# 05_-_PROFINET.net
KiCad netlist of a schematic drawn in Altium Designer
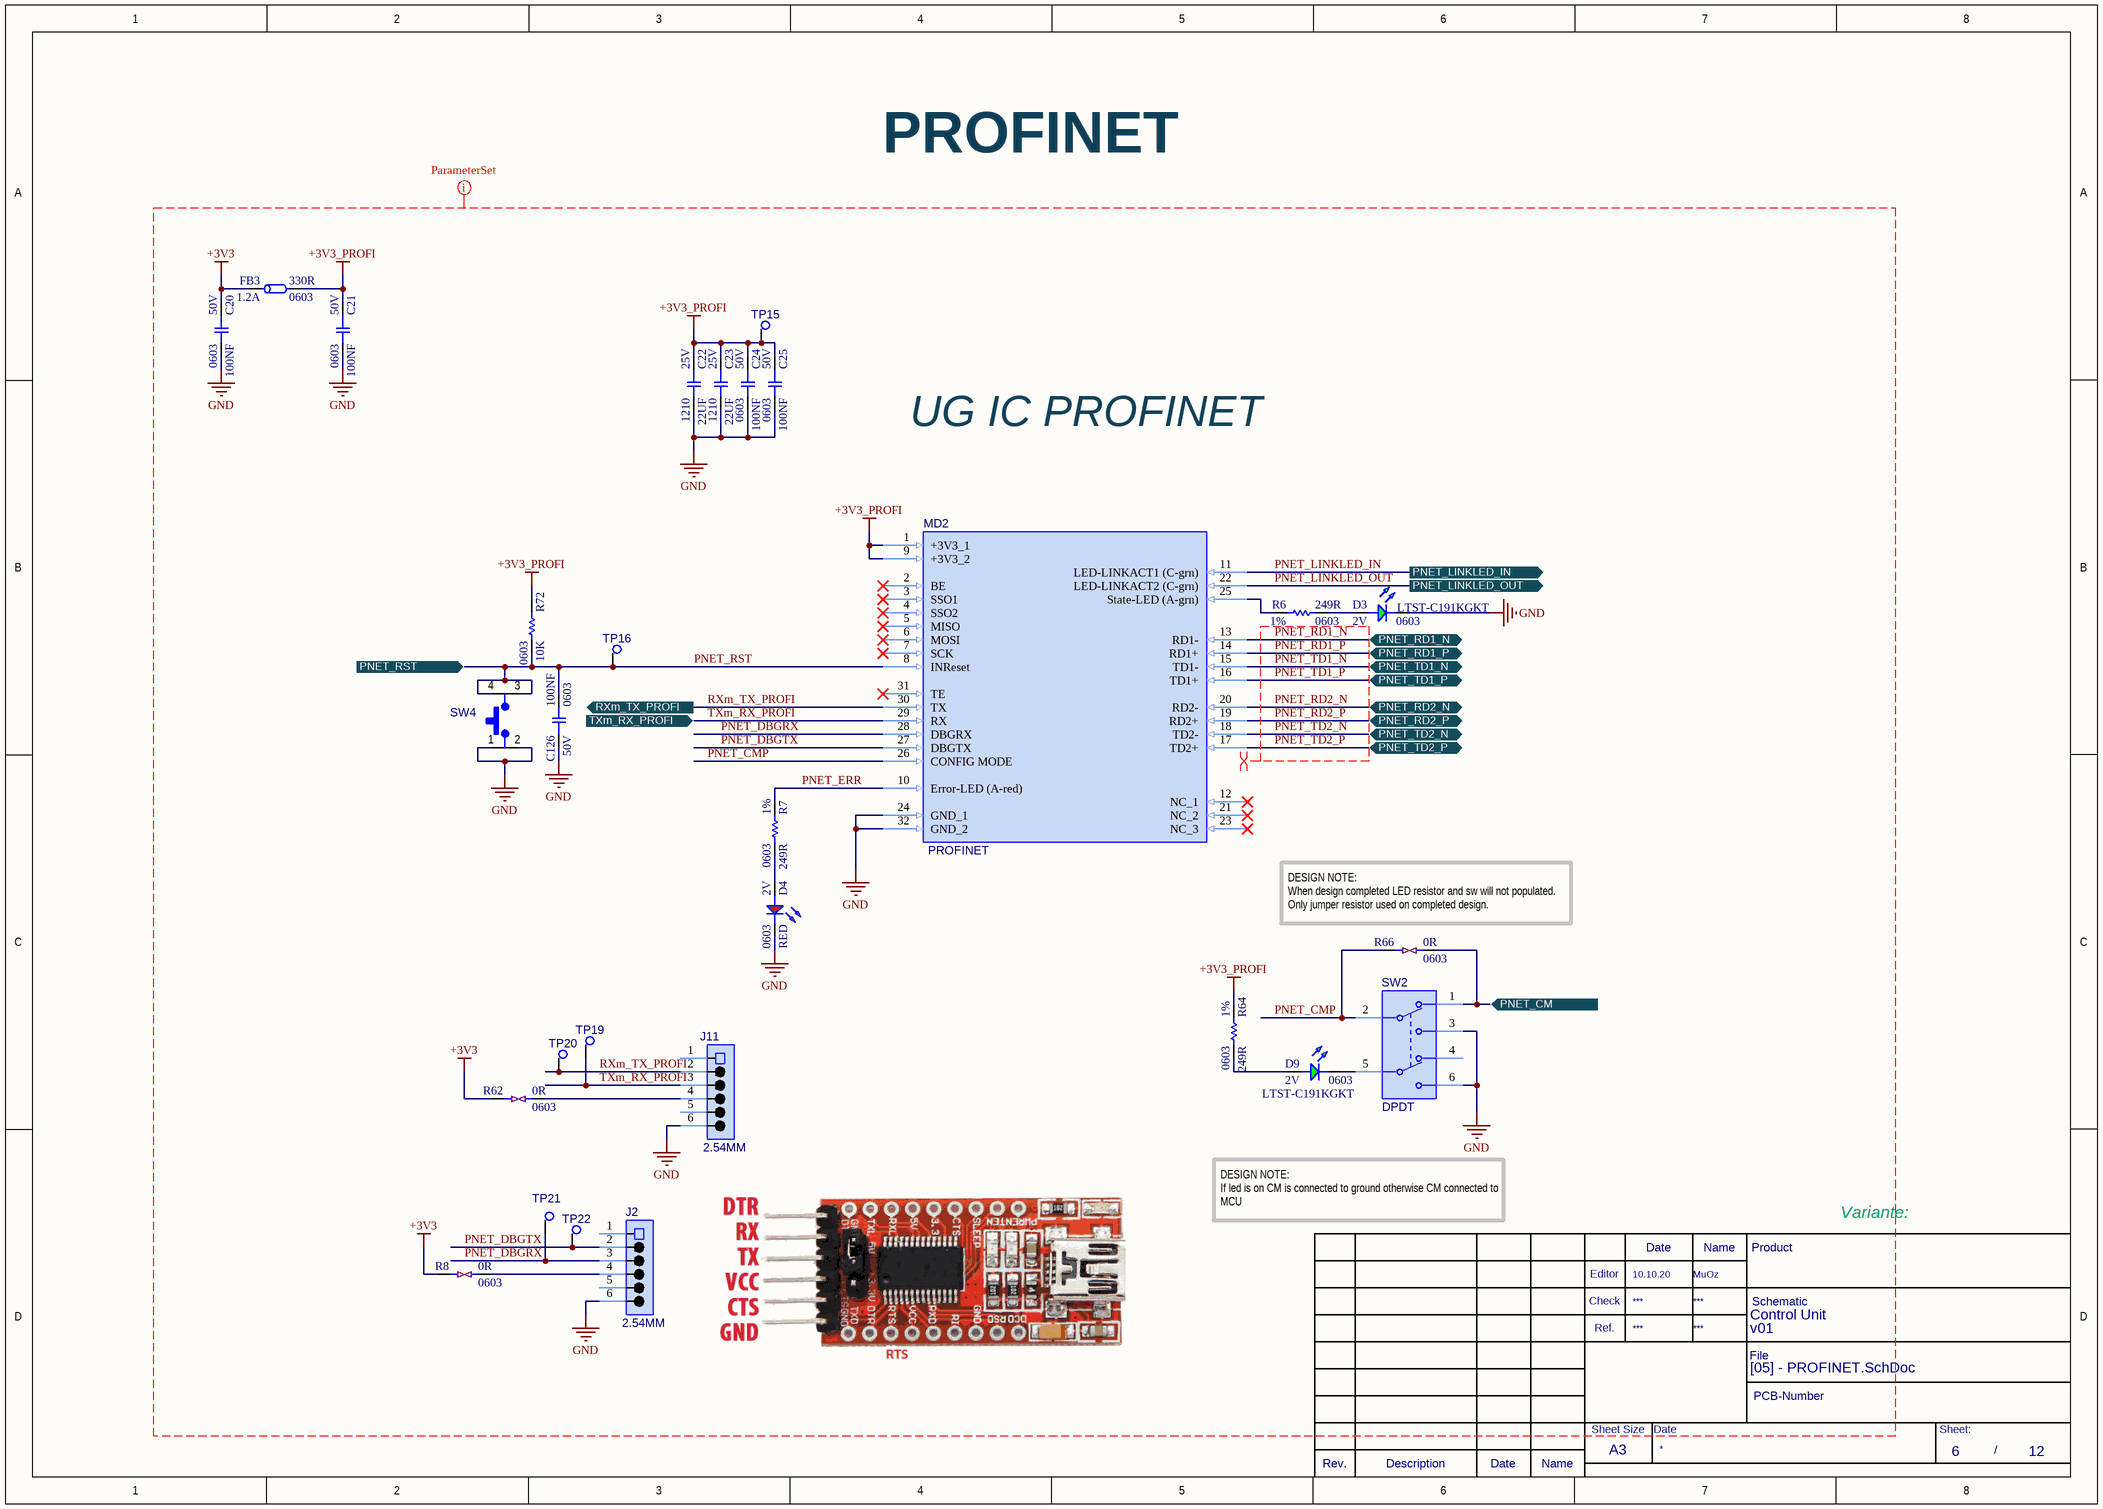
[diagram p0: [05] - PROFINET.SchDoc]

(export (version "E")
  (design (tool "Eeschema 10.0.6"))
  (components
    (comp (ref "C20")
      (value "100NF")
      (footprint "C-0603")
      (description "CAP CER 0.1UF 50V X7R 0603")
      (fields
        (field (name "MANUFACTURER") "TDK")
        (field (name "MANUFACTURER PART NUMBER") "C1608X7R1H104K080AA")
        (field (name "VOLTAGE RATING") "50V")
        (field (name "CASE CODE (IMPERIAL)") "0603")
        (field (name ".CREATOR") "F:TALI")
      )
      (libsource (lib "BARKO_SCHLIB") (part "C-100NF-0603"))
    )
    (comp (ref "C21")
      (value "100NF")
      (footprint "C-0603")
      (description "CAP CER 0.1UF 50V X7R 0603")
      (fields
        (field (name "MANUFACTURER") "TDK")
        (field (name "MANUFACTURER PART NUMBER") "C1608X7R1H104K080AA")
        (field (name "VOLTAGE RATING") "50V")
        (field (name "CASE CODE (IMPERIAL)") "0603")
        (field (name ".CREATOR") "F:TALI")
      )
      (libsource (lib "BARKO_SCHLIB") (part "C-100NF-0603"))
    )
    (comp (ref "C22")
      (value "22UF")
      (footprint "C-1210")
      (description "CAP CER 22UF 25V X7R 1210")
      (fields
        (field (name "MANUFACTURER") "Samsung")
        (field (name "MANUFACTURER PART NUMBER") "CL32B226KAJNNNE")
        (field (name "VOLTAGE RATING") "25V")
        (field (name "CASE CODE (IMPERIAL)") "1210")
        (field (name ".CREATOR") "F:TALI")
      )
      (libsource (lib "BARKO_SCHLIB") (part "C-22UF-1210"))
    )
    (comp (ref "C23")
      (value "22UF")
      (footprint "C-1210")
      (description "CAP CER 22UF 25V X7R 1210")
      (fields
        (field (name "MANUFACTURER") "Samsung")
        (field (name "MANUFACTURER PART NUMBER") "CL32B226KAJNNNE")
        (field (name "VOLTAGE RATING") "25V")
        (field (name "CASE CODE (IMPERIAL)") "1210")
        (field (name ".CREATOR") "F:TALI")
      )
      (libsource (lib "BARKO_SCHLIB") (part "C-22UF-1210"))
    )
    (comp (ref "C24")
      (value "100NF")
      (footprint "C-0603")
      (description "CAP CER 0.1UF 50V X7R 0603")
      (fields
        (field (name "MANUFACTURER") "TDK")
        (field (name "MANUFACTURER PART NUMBER") "C1608X7R1H104K080AA")
        (field (name "VOLTAGE RATING") "50V")
        (field (name "CASE CODE (IMPERIAL)") "0603")
        (field (name ".CREATOR") "F:TALI")
      )
      (libsource (lib "BARKO_SCHLIB") (part "C-100NF-0603"))
    )
    (comp (ref "C25")
      (value "100NF")
      (footprint "C-0603")
      (description "CAP CER 0.1UF 50V X7R 0603")
      (fields
        (field (name "MANUFACTURER") "TDK")
        (field (name "MANUFACTURER PART NUMBER") "C1608X7R1H104K080AA")
        (field (name "VOLTAGE RATING") "50V")
        (field (name "CASE CODE (IMPERIAL)") "0603")
        (field (name ".CREATOR") "F:TALI")
      )
      (libsource (lib "BARKO_SCHLIB") (part "C-100NF-0603"))
    )
    (comp (ref "C126")
      (value "100NF")
      (footprint "C-0603")
      (description "CAP CER 0.1UF 50V X7R 0603")
      (fields
        (field (name "MANUFACTURER") "TDK")
        (field (name "MANUFACTURER PART NUMBER") "C1608X7R1H104K080AA")
        (field (name "VOLTAGE RATING") "50V")
        (field (name "CASE CODE (IMPERIAL)") "0603")
        (field (name ".CREATOR") "F:TALI")
      )
      (libsource (lib "BARKO_SCHLIB") (part "C-100NF-0603"))
    )
    (comp (ref "D3")
      (value "LTST-C191KGKT")
      (footprint "LED-0603-GREEN")
      (description "LED GREEN CLEAR 0603 SMD")
      (fields
        (field (name "MANUFACTURER") "Vishay Lite-On")
        (field (name "FORWARD VOLTAGE") "2V")
        (field (name "CASE CODE (IMPERIAL)") "0603")
        (field (name ".CREATOR") "F:TALI")
      )
      (libsource (lib "BARKO_SCHLIB") (part "LED-GREEN-0603"))
    )
    (comp (ref "D4")
      (value "RED")
      (footprint "LED-0603")
      (description "LED RED CLEAR 0603 SMD")
      (fields
        (field (name "MANUFACTURER") "Wurth Electronics")
        (field (name "MANUFACTURER PART NUMBER") "150060RS75000")
        (field (name "CASE/PACKAGE") "0603")
        (field (name "FORWARD VOLTAGE") "2V")
      )
      (libsource (lib "BARKO_SCHLIB") (part "LED-RED-0603"))
    )
    (comp (ref "D9")
      (value "LTST-C191KGKT")
      (footprint "LED-0603-GREEN")
      (description "LED GREEN CLEAR 0603 SMD")
      (fields
        (field (name "MANUFACTURER") "Vishay Lite-On")
        (field (name "FORWARD VOLTAGE") "2V")
        (field (name "CASE CODE (IMPERIAL)") "0603")
        (field (name ".CREATOR") "F:TALI")
      )
      (libsource (lib "BARKO_SCHLIB") (part "LED-GREEN-0603"))
    )
    (comp (ref "FB3")
      (value "330R")
      (footprint "FB-0603")
      (description "FERRITE BEAD 330 OHM 0603 1LN")
      (fields
        (field (name "MANUFACTURER") "Murata")
        (field (name "MANUFACTURER PART NUMBER") "BLM18PG331SN1D")
        (field (name "CASE/PACKAGE") "0603")
        (field (name "DC CURRENT") "1.2A")
        (field (name ".CREATOR") "M.OZKAN")
      )
      (libsource (lib "BARKO_SCHLIB") (part "FB-330R-0603"))
    )
    (comp (ref "J2")
      (value "2.54MM")
      (footprint "CON-1X6-VERT-2.54MM")
      (description "CONN RCPT 6POS 0.1 TIN PCB")
      (fields (field (name "MANUFACTURER PART NUMBER") "M20-7820646"))
      (libsource (lib "SCHLIB") (part "CON-6POS-2.54MM"))
    )
    (comp (ref "J11")
      (value "2.54MM")
      (footprint "CON-1X6-VERT-2.54MM")
      (description "CONN RCPT 6POS 0.1 TIN PCB")
      (fields (field (name "MANUFACTURER PART NUMBER") "M20-7820646"))
      (libsource (lib "SCHLIB") (part "CON-6POS-2.54MM"))
    )
    (comp (ref "MD2")
      (value "PROFINET")
      (footprint "MD-UG-IC-PIN")
      (description "UNIGATE® IC - PROFINET 2Port")
      (libsource (lib "SCHLIB") (part "MD-UG IC PROFINET"))
    )
    (comp (ref "R6")
      (value "249R")
      (footprint "R-0603")
      (description "RES 249 OHM 1% 1/10W 0603")
      (fields
        (field (name "MANUFACTURER") "Stackpole Electronics")
        (field (name "MANUFACTURER PART NUMBER") "RMCF0603FT249R")
        (field (name "TOLERANCE") "1%")
        (field (name "CASE/PACKAGE") "0603")
      )
      (libsource (lib "BARKO_SCHLIB") (part "R-249R-0603"))
    )
    (comp (ref "R7")
      (value "249R")
      (footprint "R-0603")
      (description "RES 249 OHM 1% 1/10W 0603")
      (fields
        (field (name "MANUFACTURER") "Stackpole Electronics")
        (field (name "MANUFACTURER PART NUMBER") "RMCF0603FT249R")
        (field (name "TOLERANCE") "1%")
        (field (name "CASE/PACKAGE") "0603")
      )
      (libsource (lib "BARKO_SCHLIB") (part "R-249R-0603"))
    )
    (comp (ref "R8")
      (value "0R")
      (footprint "JMP-0603")
      (description "RES SMD 0 OHM 1/10W JUMP 0603")
      (fields
        (field (name "MANUFACTURER") "Yageo")
        (field (name "MANUFACTURER PART NUMBER") "RC0603JR-070RL")
        (field (name "CASE CODE (IMPERIAL)") "0603")
        (field (name ".CREATOR") "F:TALI")
      )
      (libsource (lib "BARKO_SCHLIB") (part "R-0R-0603"))
    )
    (comp (ref "R62")
      (value "0R")
      (footprint "JMP-0603")
      (description "RES SMD 0 OHM 1/10W JUMP 0603")
      (fields
        (field (name "MANUFACTURER") "Yageo")
        (field (name "MANUFACTURER PART NUMBER") "RC0603JR-070RL")
        (field (name "CASE CODE (IMPERIAL)") "0603")
        (field (name ".CREATOR") "F:TALI")
      )
      (libsource (lib "BARKO_SCHLIB") (part "R-0R-0603"))
    )
    (comp (ref "R64")
      (value "249R")
      (footprint "R-0603")
      (description "RES 249 OHM 1% 1/10W 0603")
      (fields
        (field (name "MANUFACTURER") "Stackpole Electronics")
        (field (name "MANUFACTURER PART NUMBER") "RMCF0603FT249R")
        (field (name "TOLERANCE") "1%")
        (field (name "CASE/PACKAGE") "0603")
      )
      (libsource (lib "BARKO_SCHLIB") (part "R-249R-0603"))
    )
    (comp (ref "R66")
      (value "0R")
      (footprint "JMP-0603")
      (description "RES SMD 0 OHM 1/10W JUMP 0603")
      (fields
        (field (name "MANUFACTURER") "Yageo")
        (field (name "MANUFACTURER PART NUMBER") "RC0603JR-070RL")
        (field (name "CASE CODE (IMPERIAL)") "0603")
        (field (name ".CREATOR") "F:TALI")
      )
      (libsource (lib "BARKO_SCHLIB") (part "R-0R-0603"))
    )
    (comp (ref "R72")
      (value "10K")
      (footprint "R-0603")
      (description "RES SMD 10K OHM 1% 1/10W 0603")
      (fields
        (field (name "MANUFACTURER") "Yageo")
        (field (name "MANUFACTURER PART NUMBER") "RC0603FR-0710KL")
        (field (name "CASE CODE (IMPERIAL)") "0603")
        (field (name ".CREATOR") "F:TALI")
      )
      (libsource (lib "BARKO_SCHLIB") (part "R-10K-0603"))
    )
    (comp (ref "SW2")
      (value "DPDT")
      (footprint "SW-AYZ0202AGRLC")
      (description "SWITCH SLIDE DPDT 100MA 12V")
      (fields
        (field (name "MANUFACTURER") "ITT C&K")
        (field (name "MANUFACTURER PART NUMBER") "AYZ0202AGRLC")
      )
      (libsource (lib "SCHLIB") (part "SW-AYZ0202AGRLC"))
    )
    (comp (ref "SW4")
      (value "SW-TACTILE-5MM")
      (footprint "TACTILE_SMD_V2")
      (description "SWITCH TACTILE SPST-NO 0.05A 24V")
      (fields
        (field (name "MANUFACTURER") "TE Connectivity AMP")
        (field (name "MANUFACTURER PART NUMBER") "FSM4JSMA")
        (field (name ".CREATOR") "F:TALI")
      )
      (libsource (lib "BARKO_SCHLIB") (part "SW-TACTILE-5MM"))
    )
    (comp (ref "TP15")
      (value "MECH-TESTPOINT")
      (footprint "MECH-TESTPOINT")
      (fields (field (name ".CREATOR") "F:TALI"))
      (libsource (lib "BARKO_SCHLIB") (part "MECH-TESTPOINT"))
    )
    (comp (ref "TP16")
      (value "MECH-TESTPOINT")
      (footprint "MECH-TESTPOINT")
      (fields (field (name ".CREATOR") "F:TALI"))
      (libsource (lib "BARKO_SCHLIB") (part "MECH-TESTPOINT"))
    )
    (comp (ref "TP19")
      (value "MECH-TESTPOINT")
      (footprint "MECH-TESTPOINT")
      (fields (field (name ".CREATOR") "F:TALI"))
      (libsource (lib "BARKO_SCHLIB") (part "MECH-TESTPOINT"))
    )
    (comp (ref "TP20")
      (value "MECH-TESTPOINT")
      (footprint "MECH-TESTPOINT")
      (fields (field (name ".CREATOR") "F:TALI"))
      (libsource (lib "BARKO_SCHLIB") (part "MECH-TESTPOINT"))
    )
    (comp (ref "TP21")
      (value "MECH-TESTPOINT")
      (footprint "MECH-TESTPOINT")
      (fields (field (name ".CREATOR") "F:TALI"))
      (libsource (lib "BARKO_SCHLIB") (part "MECH-TESTPOINT"))
    )
    (comp (ref "TP22")
      (value "MECH-TESTPOINT")
      (footprint "MECH-TESTPOINT")
      (fields (field (name ".CREATOR") "F:TALI"))
      (libsource (lib "BARKO_SCHLIB") (part "MECH-TESTPOINT"))
    )
  )
  (nets
    (net (code "1") (name "+3V3") (class "Default")
      (node (ref "C20") (pin "1") (pinfunction "1_1") (pintype "passive"))
      (node (ref "FB3") (pin "1") (pinfunction "1_1") (pintype "passive"))
      (node (ref "R62") (pin "1") (pinfunction "1_1") (pintype "passive"))
      (node (ref "R8") (pin "1") (pinfunction "1_1") (pintype "passive"))
    )
    (net (code "2") (name "+3V3_PROFI") (class "Default")
      (node (ref "C21") (pin "1") (pinfunction "1_1") (pintype "passive"))
      (node (ref "C22") (pin "1") (pinfunction "1_1") (pintype "passive"))
      (node (ref "C23") (pin "1") (pinfunction "1_1") (pintype "passive"))
      (node (ref "C24") (pin "1") (pinfunction "1_1") (pintype "passive"))
      (node (ref "C25") (pin "1") (pinfunction "1_1") (pintype "passive"))
      (node (ref "FB3") (pin "2") (pinfunction "2_2") (pintype "passive"))
      (node (ref "MD2") (pin "1") (pinfunction "+3V3_1_1") (pintype "input"))
      (node (ref "MD2") (pin "9") (pinfunction "+3V3_2_9") (pintype "input"))
      (node (ref "R64") (pin "1") (pinfunction "1_1") (pintype "passive"))
      (node (ref "R72") (pin "1") (pinfunction "1_1") (pintype "passive"))
      (node (ref "TP15") (pin "1") (pinfunction "1_1") (pintype "passive"))
    )
    (net (code "3") (name "/PNET_CM") (class "Default")
      (node (ref "R66") (pin "2") (pinfunction "2_2") (pintype "passive"))
      (node (ref "SW2") (pin "1") (pinfunction "1_1") (pintype "passive"))
    )
    (net (code "4") (name "/PNET_CMP") (class "Default")
      (node (ref "MD2") (pin "26") (pinfunction "CONFIG_MODE_26") (pintype "input"))
      (node (ref "R66") (pin "1") (pinfunction "1_1") (pintype "passive"))
      (node (ref "SW2") (pin "2") (pinfunction "2_2") (pintype "passive"))
    )
    (net (code "5") (name "/PNET_DBGRX") (class "Default")
      (node (ref "J2") (pin "3") (pinfunction "3_3") (pintype "passive"))
      (node (ref "MD2") (pin "28") (pinfunction "DBGRX_28") (pintype "input"))
      (node (ref "TP21") (pin "1") (pinfunction "1_1") (pintype "passive"))
    )
    (net (code "6") (name "/PNET_DBGTX") (class "Default")
      (node (ref "J2") (pin "2") (pinfunction "2_2") (pintype "passive"))
      (node (ref "MD2") (pin "27") (pinfunction "DBGTX_27") (pintype "input"))
      (node (ref "TP22") (pin "1") (pinfunction "1_1") (pintype "passive"))
    )
    (net (code "7") (name "/PNET_ERR") (class "Default")
      (node (ref "MD2") (pin "10") (pinfunction "Error-LED_(A-red)_10") (pintype "input"))
      (node (ref "R7") (pin "1") (pinfunction "1_1") (pintype "passive"))
    )
    (net (code "8") (name "/PNET_LINKLED_IN") (class "Default")
      (node (ref "MD2") (pin "11") (pinfunction "LED-LINKACT1_(C-grn)_11") (pintype "input"))
    )
    (net (code "9") (name "/PNET_LINKLED_OUT") (class "Default")
      (node (ref "MD2") (pin "22") (pinfunction "LED-LINKACT2_(C-grn)_22") (pintype "input"))
    )
    (net (code "10") (name "/PNET_RD1_N") (class "Default")
      (node (ref "MD2") (pin "13") (pinfunction "RD1-_13") (pintype "input"))
    )
    (net (code "11") (name "/PNET_RD1_P") (class "Default")
      (node (ref "MD2") (pin "14") (pinfunction "RD1+_14") (pintype "input"))
    )
    (net (code "12") (name "/PNET_RD2_N") (class "Default")
      (node (ref "MD2") (pin "20") (pinfunction "RD2-_20") (pintype "input"))
    )
    (net (code "13") (name "/PNET_RD2_P") (class "Default")
      (node (ref "MD2") (pin "19") (pinfunction "RD2+_19") (pintype "input"))
    )
    (net (code "14") (name "/PNET_RST") (class "Default")
      (node (ref "C126") (pin "2") (pinfunction "2_2") (pintype "passive"))
      (node (ref "MD2") (pin "8") (pinfunction "INReset_8") (pintype "input"))
      (node (ref "R72") (pin "2") (pinfunction "2_2") (pintype "passive"))
      (node (ref "SW4") (pin "3") (pinfunction "3_3") (pintype "passive"))
      (node (ref "SW4") (pin "4") (pinfunction "4_4") (pintype "passive"))
      (node (ref "TP16") (pin "1") (pinfunction "1_1") (pintype "passive"))
    )
    (net (code "15") (name "/PNET_TD1_N") (class "Default")
      (node (ref "MD2") (pin "15") (pinfunction "TD1-_15") (pintype "input"))
    )
    (net (code "16") (name "/PNET_TD1_P") (class "Default")
      (node (ref "MD2") (pin "16") (pinfunction "TD1+_16") (pintype "input"))
    )
    (net (code "17") (name "/PNET_TD2_N") (class "Default")
      (node (ref "MD2") (pin "18") (pinfunction "TD2-_18") (pintype "input"))
    )
    (net (code "18") (name "/PNET_TD2_P") (class "Default")
      (node (ref "MD2") (pin "17") (pinfunction "TD2+_17") (pintype "input"))
    )
    (net (code "19") (name "/RXm_TX_PROFI") (class "Default")
      (node (ref "J11") (pin "2") (pinfunction "2_2") (pintype "passive"))
      (node (ref "MD2") (pin "30") (pinfunction "TX_30") (pintype "input"))
      (node (ref "TP20") (pin "1") (pinfunction "1_1") (pintype "passive"))
    )
    (net (code "20") (name "/TXm_RX_PROFI") (class "Default")
      (node (ref "J11") (pin "3") (pinfunction "3_3") (pintype "passive"))
      (node (ref "MD2") (pin "29") (pinfunction "RX_29") (pintype "input"))
      (node (ref "TP19") (pin "1") (pinfunction "1_1") (pintype "passive"))
    )
    (net (code "21") (name "GND") (class "Default")
      (node (ref "C126") (pin "1") (pinfunction "1_1") (pintype "passive"))
      (node (ref "C20") (pin "2") (pinfunction "2_2") (pintype "passive"))
      (node (ref "C21") (pin "2") (pinfunction "2_2") (pintype "passive"))
      (node (ref "C22") (pin "2") (pinfunction "2_2") (pintype "passive"))
      (node (ref "C23") (pin "2") (pinfunction "2_2") (pintype "passive"))
      (node (ref "C24") (pin "2") (pinfunction "2_2") (pintype "passive"))
      (node (ref "C25") (pin "2") (pinfunction "2_2") (pintype "passive"))
      (node (ref "D3") (pin "C") (pinfunction "C_C") (pintype "passive"))
      (node (ref "D4") (pin "C") (pinfunction "C_C") (pintype "passive"))
      (node (ref "J11") (pin "6") (pinfunction "6_6") (pintype "passive"))
      (node (ref "J2") (pin "6") (pinfunction "6_6") (pintype "passive"))
      (node (ref "MD2") (pin "24") (pinfunction "GND_1_24") (pintype "input"))
      (node (ref "MD2") (pin "32") (pinfunction "GND_2_32") (pintype "input"))
      (node (ref "SW2") (pin "3") (pinfunction "3_3") (pintype "passive"))
      (node (ref "SW2") (pin "6") (pinfunction "6_6") (pintype "passive"))
      (node (ref "SW4") (pin "1") (pinfunction "1_1") (pintype "passive"))
      (node (ref "SW4") (pin "2") (pinfunction "2_2") (pintype "passive"))
    )
    (net (code "22") (name "Net-(D3-PadA)") (class "Default")
      (node (ref "D3") (pin "A") (pinfunction "A_A") (pintype "passive"))
      (node (ref "R6") (pin "2") (pinfunction "2_2") (pintype "passive"))
    )
    (net (code "23") (name "Net-(D4-PadA)") (class "Default")
      (node (ref "D4") (pin "A") (pinfunction "A_A") (pintype "passive"))
      (node (ref "R7") (pin "2") (pinfunction "2_2") (pintype "passive"))
    )
    (net (code "24") (name "Net-(D9-PadA)") (class "Default")
      (node (ref "D9") (pin "A") (pinfunction "A_A") (pintype "passive"))
      (node (ref "R64") (pin "2") (pinfunction "2_2") (pintype "passive"))
    )
    (net (code "25") (name "Net-(D9-PadC)") (class "Default")
      (node (ref "D9") (pin "C") (pinfunction "C_C") (pintype "passive"))
      (node (ref "SW2") (pin "5") (pinfunction "5_5") (pintype "passive"))
    )
    (net (code "26") (name "Net-(J2-Pad4)") (class "Default")
      (node (ref "J2") (pin "4") (pinfunction "4_4") (pintype "passive"))
      (node (ref "R8") (pin "2") (pinfunction "2_2") (pintype "passive"))
    )
    (net (code "27") (name "Net-(J11-Pad4)") (class "Default")
      (node (ref "J11") (pin "4") (pinfunction "4_4") (pintype "passive"))
      (node (ref "R62") (pin "2") (pinfunction "2_2") (pintype "passive"))
    )
    (net (code "28") (name "Net-(MD2-State-LED_(A-grn))") (class "Default")
      (node (ref "MD2") (pin "25") (pinfunction "State-LED_(A-grn)_25") (pintype "input"))
      (node (ref "R6") (pin "1") (pinfunction "1_1") (pintype "passive"))
    )
    (net (code "29") (name "unconnected-(J2-GND_IN-Pad1)") (class "Default")
      (node (ref "J2") (pin "1") (pinfunction "GND_IN_1") (pintype "passive"))
    )
    (net (code "30") (name "unconnected-(J2-Pad5)") (class "Default")
      (node (ref "J2") (pin "5") (pinfunction "5_5") (pintype "passive"))
    )
    (net (code "31") (name "unconnected-(J11-GND_IN-Pad1)") (class "Default")
      (node (ref "J11") (pin "1") (pinfunction "GND_IN_1") (pintype "passive"))
    )
    (net (code "32") (name "unconnected-(J11-Pad5)") (class "Default")
      (node (ref "J11") (pin "5") (pinfunction "5_5") (pintype "passive"))
    )
    (net (code "33") (name "unconnected-(MD2-BE-Pad2)") (class "Default")
      (node (ref "MD2") (pin "2") (pinfunction "BE_2") (pintype "input+no_connect"))
    )
    (net (code "34") (name "unconnected-(MD2-MISO-Pad5)") (class "Default")
      (node (ref "MD2") (pin "5") (pinfunction "MISO_5") (pintype "input+no_connect"))
    )
    (net (code "35") (name "unconnected-(MD2-MOSI-Pad6)") (class "Default")
      (node (ref "MD2") (pin "6") (pinfunction "MOSI_6") (pintype "input+no_connect"))
    )
    (net (code "36") (name "unconnected-(MD2-NC_1-Pad12)") (class "Default")
      (node (ref "MD2") (pin "12") (pinfunction "NC_1_12") (pintype "input+no_connect"))
    )
    (net (code "37") (name "unconnected-(MD2-NC_2-Pad21)") (class "Default")
      (node (ref "MD2") (pin "21") (pinfunction "NC_2_21") (pintype "input+no_connect"))
    )
    (net (code "38") (name "unconnected-(MD2-NC_3-Pad23)") (class "Default")
      (node (ref "MD2") (pin "23") (pinfunction "NC_3_23") (pintype "input+no_connect"))
    )
    (net (code "39") (name "unconnected-(MD2-SCK-Pad7)") (class "Default")
      (node (ref "MD2") (pin "7") (pinfunction "SCK_7") (pintype "input+no_connect"))
    )
    (net (code "40") (name "unconnected-(MD2-SSO1-Pad3)") (class "Default")
      (node (ref "MD2") (pin "3") (pinfunction "SSO1_3") (pintype "input+no_connect"))
    )
    (net (code "41") (name "unconnected-(MD2-SSO2-Pad4)") (class "Default")
      (node (ref "MD2") (pin "4") (pinfunction "SSO2_4") (pintype "input+no_connect"))
    )
    (net (code "42") (name "unconnected-(MD2-TE-Pad31)") (class "Default")
      (node (ref "MD2") (pin "31") (pinfunction "TE_31") (pintype "input+no_connect"))
    )
    (net (code "43") (name "unconnected-(SW2-Pad4)") (class "Default")
      (node (ref "SW2") (pin "4") (pinfunction "4_4") (pintype "passive"))
    )
  )
)
